# SD_Card.net
KiCad netlist of a schematic drawn in EasyEDA
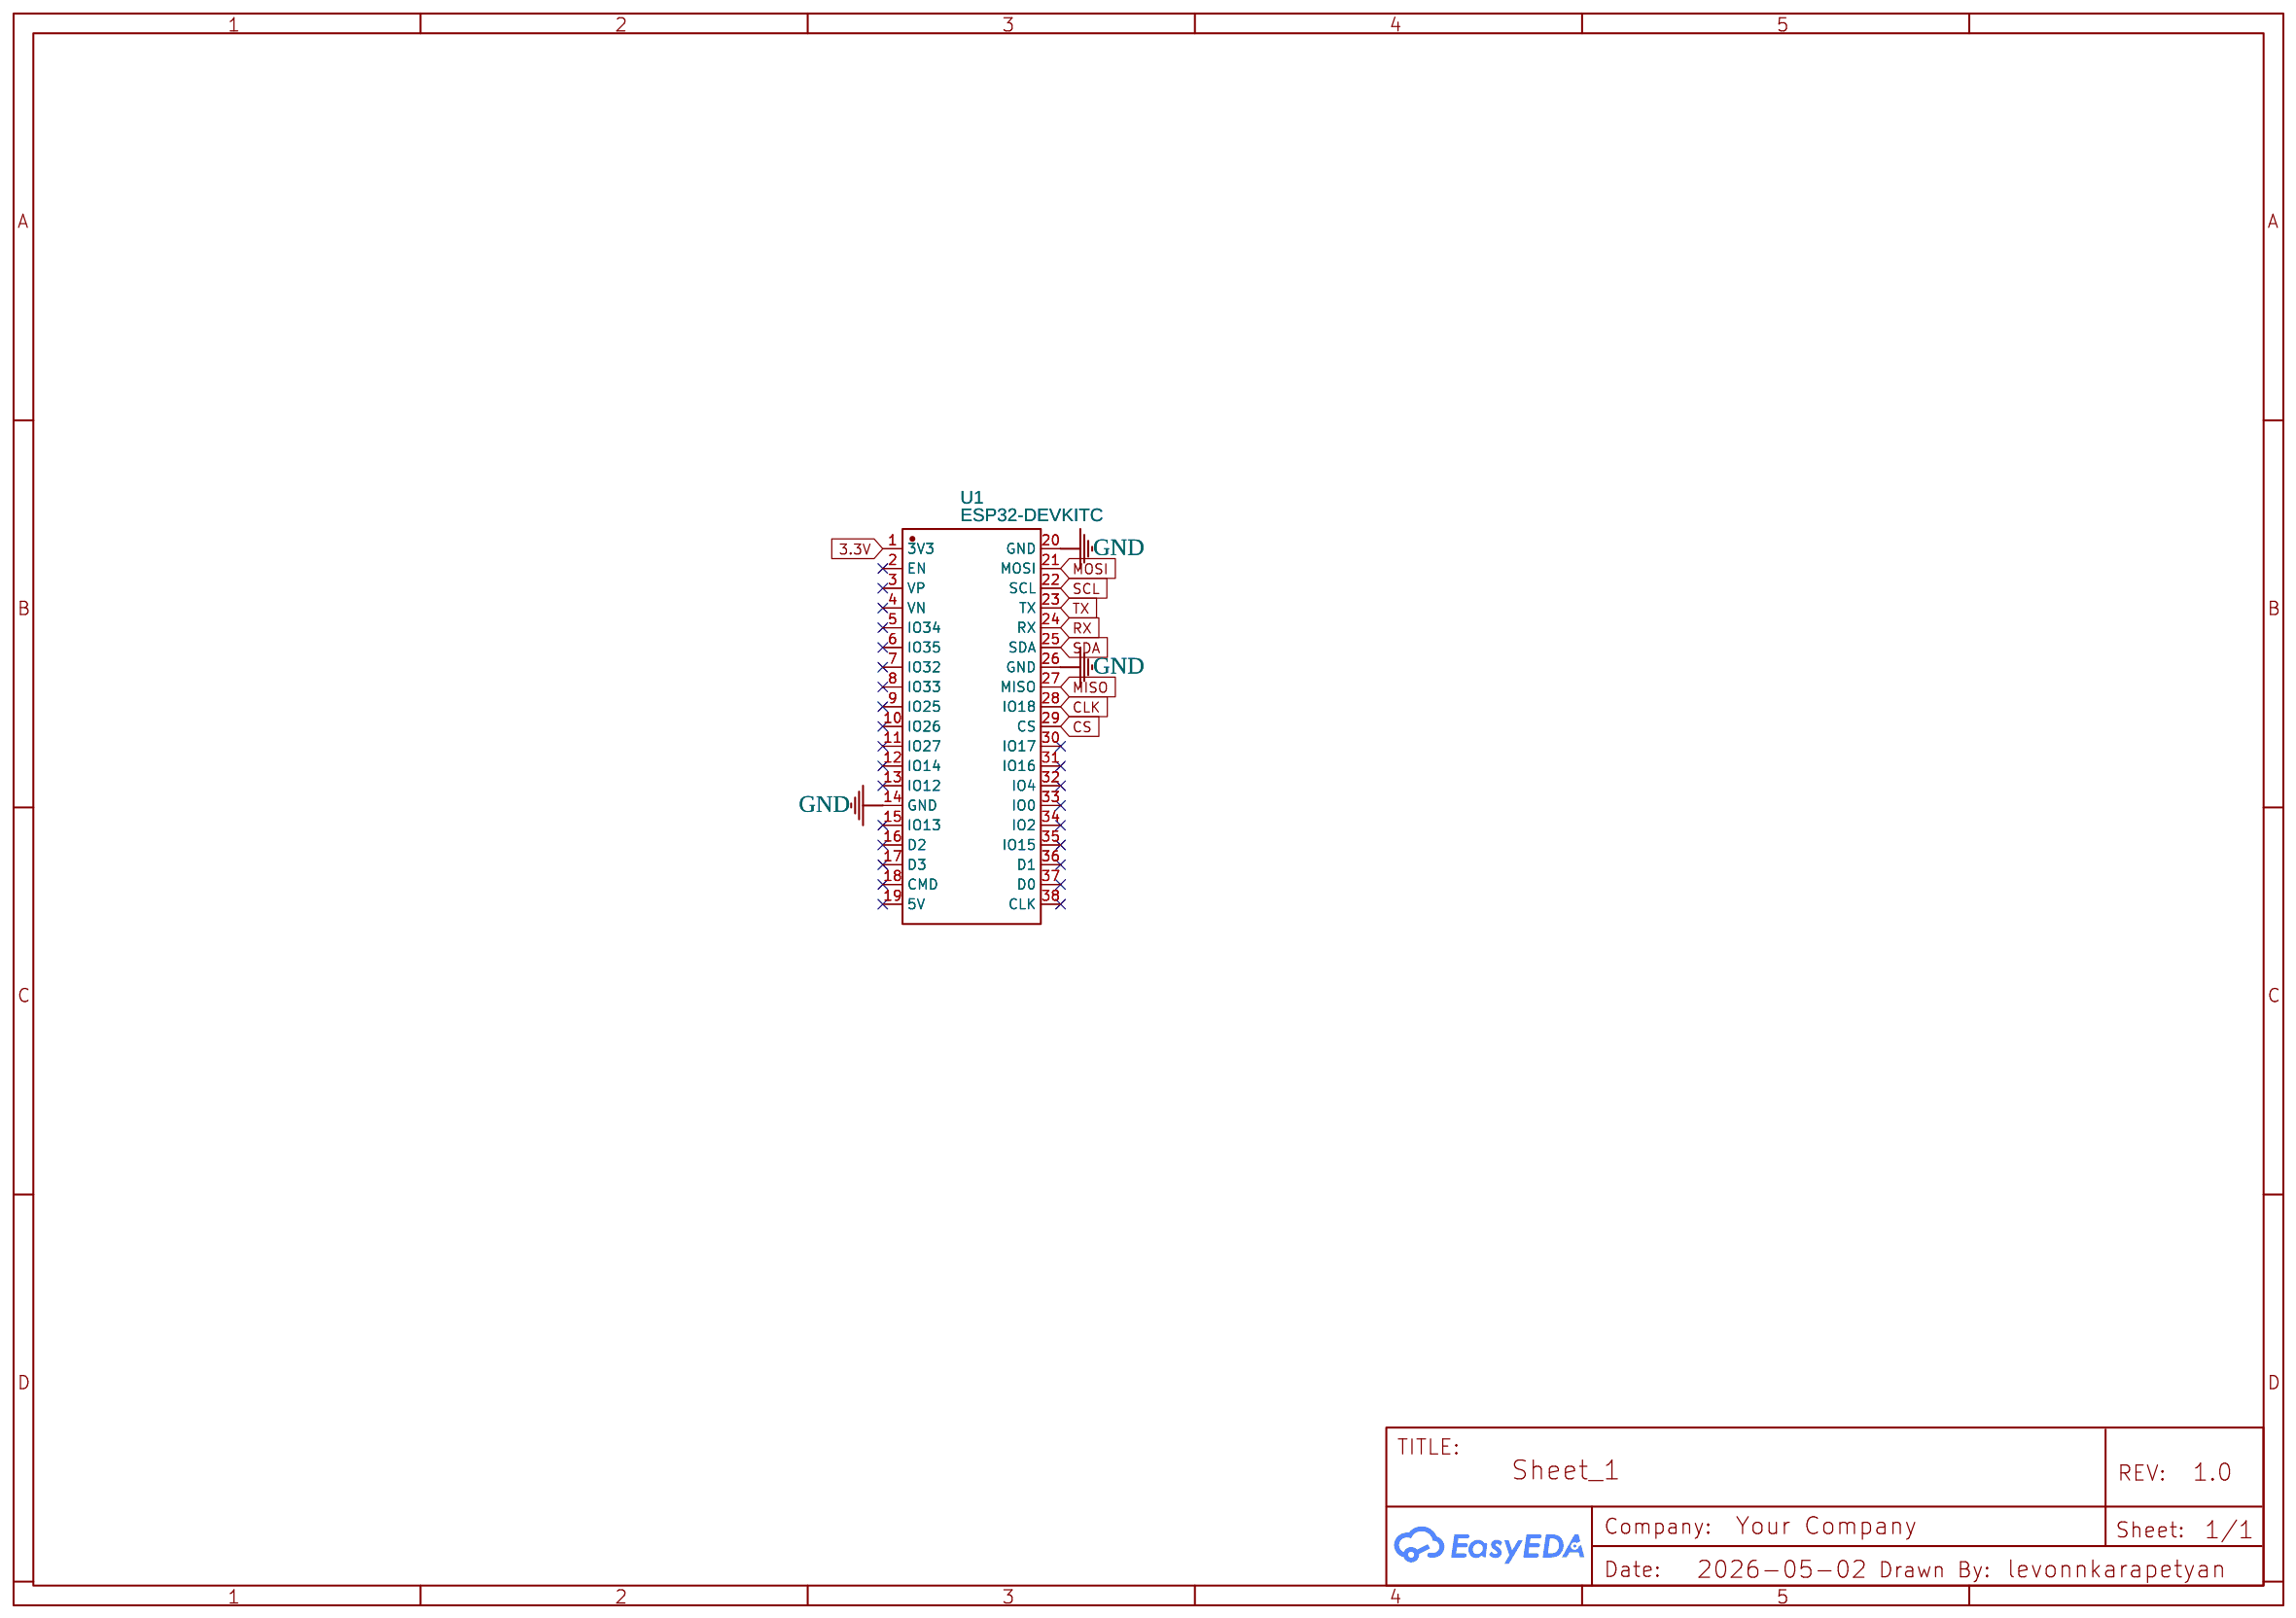
[diagram p0: ESP32]
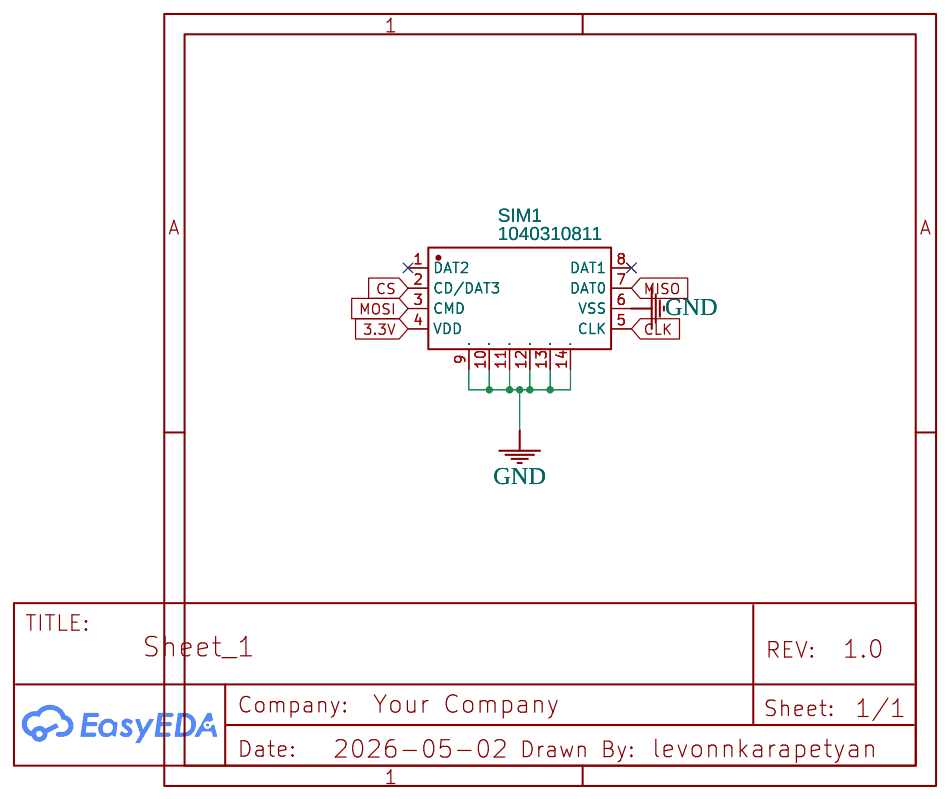
[diagram p1: SD_CARD]
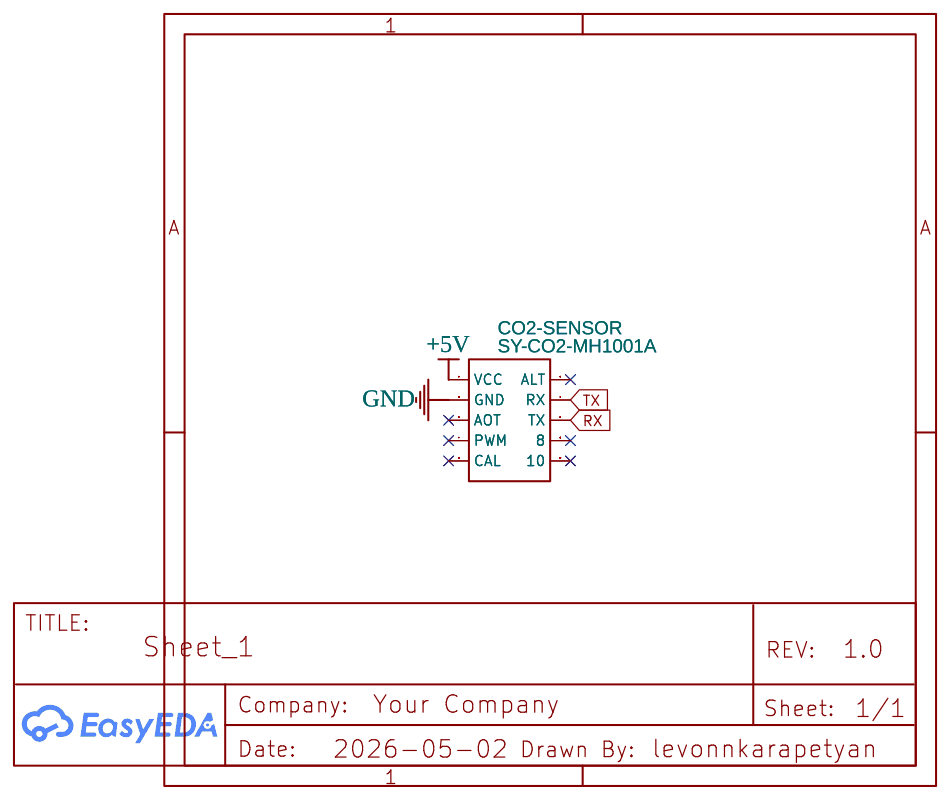
[diagram p2: CO2_sensor]
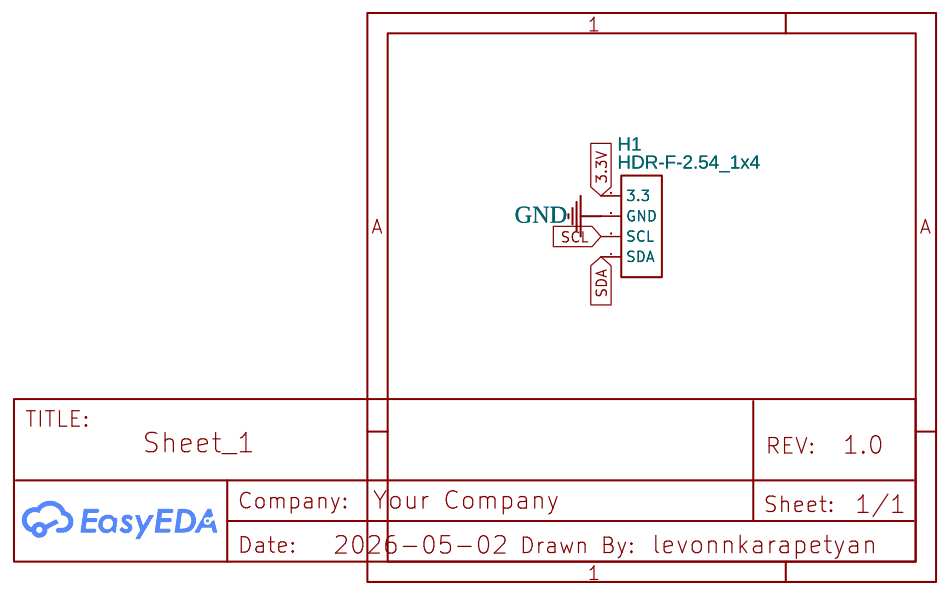
[diagram p3: BME280]
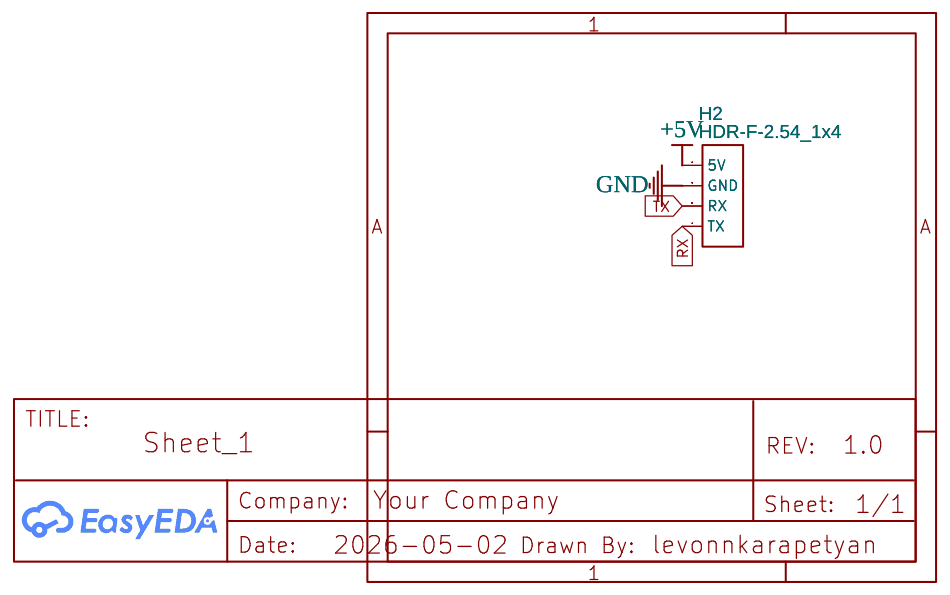
[diagram p4: PMS5003]
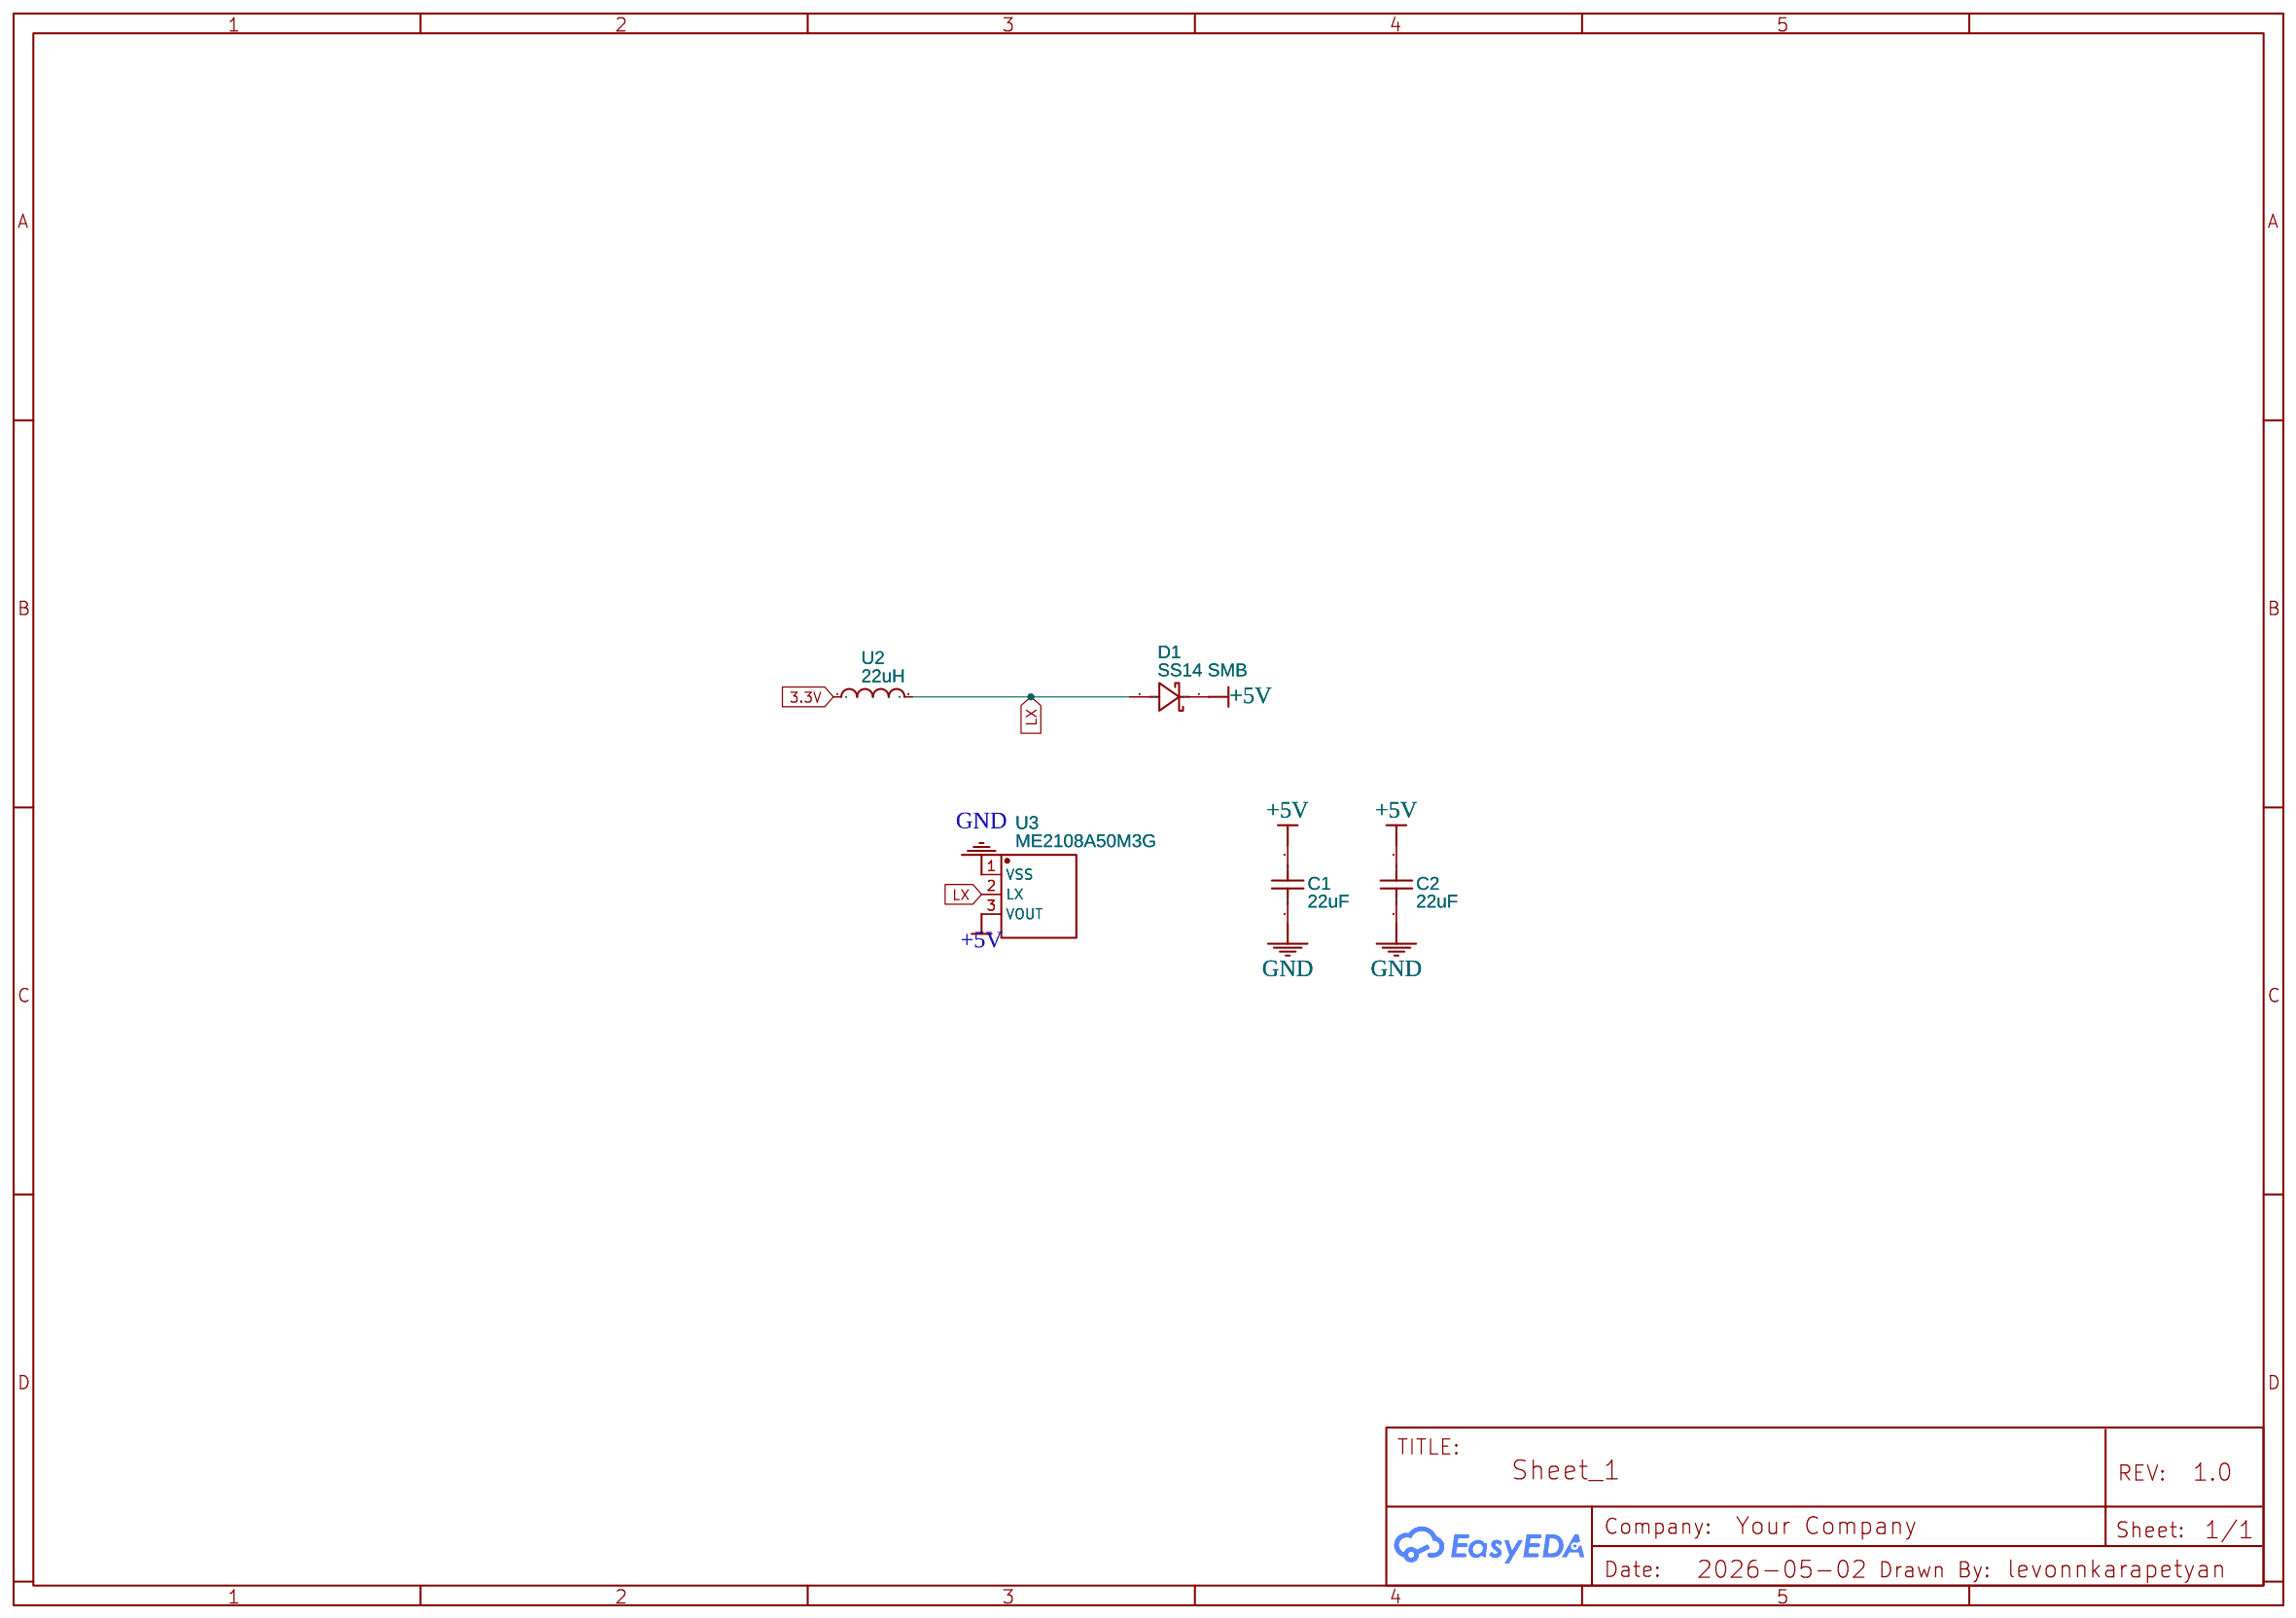
[diagram p5: Booster]

(export (version "E")
  (design (tool "Eeschema 10.0.6"))
  (components
    (comp (ref "U1")
      (value "ESP32-DEVKITC")
      (fields
        (field (name "Manufacturer Part") "ESP32-DevKitC")
        (field (name "Manufacturer") "ESPRESSIF(乐鑫)")
      )
      (libsource (lib "") (part "ESP32-DEVKITC"))
    )
    (comp (ref "SIM1")
      (value "1040310811")
      (fields (field (name "Manufacturer") "MOLEX"))
      (libsource (lib "") (part "1040310811"))
    )
    (comp (ref "CO2-SENSOR") (value "SY-CO2-MH1001A") (libsource (lib "") (part "HDR-F-2.54_2x5")))
    (comp (ref "H1") (value "HDR-F-2.54_1x4") (libsource (lib "") (part "HDR-F-2.54_1x4")))
    (comp (ref "H2") (value "HDR-F-2.54_1x4") (libsource (lib "") (part "HDR-F-2.54_1x4")))
    (comp (ref "C1")
      (value "22uF")
      (fields
        (field (name "Manufacturer Part") "CL21A226MAYNNNE")
        (field (name "Manufacturer") "SAMSUNG(三星)")
      )
      (libsource (lib "") (part "CL21A226MAYNNNE"))
    )
    (comp (ref "C2")
      (value "22uF")
      (fields
        (field (name "Manufacturer Part") "CL21A226MAYNNNE")
        (field (name "Manufacturer") "SAMSUNG(三星)")
      )
      (libsource (lib "") (part "CL21A226MAYNNNE"))
    )
    (comp (ref "D1")
      (value "SS14 SMB")
      (fields (field (name "Manufacturer") "BORN(伯恩半导体)"))
      (libsource (lib "") (part "SS14 SMB"))
    )
    (comp (ref "U2")
      (value "22uH")
      (fields (field (name "Manufacturer Part") "APH0630T220M") (field (name "Manufacturer") "APV(爱普微)"))
      (libsource (lib "") (part "APH0630T220M"))
    )
    (comp (ref "U3")
      (value "ME2108A50M3G")
      (fields (field (name "Manufacturer") "MICRONE(南京微盟)"))
      (libsource (lib "") (part "ME2108A50M3G"))
    )
  )
  (nets
    (net (code "1") (name "+5V") (class "Default")
      (node (ref "C1") (pin "2") (pinfunction "2_2") (pintype "unspecified"))
      (node (ref "C2") (pin "2") (pinfunction "2_2") (pintype "unspecified"))
      (node (ref "CO2-SENSOR") (pin "1") (pinfunction "VCC_1") (pintype "unspecified"))
      (node (ref "D1") (pin "1") (pinfunction "K_1") (pintype "unspecified"))
      (node (ref "H2") (pin "1") (pinfunction "5V_1") (pintype "unspecified"))
      (node (ref "U3") (pin "3") (pinfunction "VOUT_3") (pintype "unspecified"))
    )
    (net (code "2") (name "3.3V") (class "Default")
      (node (ref "H1") (pin "1") (pinfunction "3.3_1") (pintype "unspecified"))
      (node (ref "SIM1") (pin "4") (pinfunction "VDD_4") (pintype "unspecified"))
      (node (ref "U1") (pin "1") (pinfunction "3V3_1") (pintype "unspecified"))
      (node (ref "U2") (pin "1") (pinfunction "1_1") (pintype "unspecified"))
    )
    (net (code "3") (name "CLK") (class "Default")
      (node (ref "SIM1") (pin "5") (pinfunction "CLK_5") (pintype "unspecified"))
      (node (ref "U1") (pin "28") (pinfunction "IO18_28") (pintype "unspecified"))
    )
    (net (code "4") (name "CS") (class "Default")
      (node (ref "SIM1") (pin "2") (pinfunction "CD/DAT3_2") (pintype "unspecified"))
      (node (ref "U1") (pin "29") (pinfunction "CS_29") (pintype "unspecified"))
    )
    (net (code "5") (name "GND") (class "Default")
      (node (ref "C1") (pin "1") (pinfunction "1_1") (pintype "unspecified"))
      (node (ref "C2") (pin "1") (pinfunction "1_1") (pintype "unspecified"))
      (node (ref "CO2-SENSOR") (pin "3") (pinfunction "GND_3") (pintype "unspecified"))
      (node (ref "H1") (pin "2") (pinfunction "GND_2") (pintype "unspecified"))
      (node (ref "H2") (pin "2") (pinfunction "GND_2") (pintype "unspecified"))
      (node (ref "SIM1") (pin "10") (pinfunction "10_10") (pintype "unspecified"))
      (node (ref "SIM1") (pin "11") (pinfunction "11_11") (pintype "unspecified"))
      (node (ref "SIM1") (pin "12") (pinfunction "12_12") (pintype "unspecified"))
      (node (ref "SIM1") (pin "13") (pinfunction "13_13") (pintype "unspecified"))
      (node (ref "SIM1") (pin "14") (pinfunction "14_14") (pintype "unspecified"))
      (node (ref "SIM1") (pin "6") (pinfunction "VSS_6") (pintype "unspecified"))
      (node (ref "SIM1") (pin "9") (pinfunction "9_9") (pintype "unspecified"))
      (node (ref "U1") (pin "14") (pinfunction "GND_14") (pintype "unspecified"))
      (node (ref "U1") (pin "20") (pinfunction "GND_20") (pintype "unspecified"))
      (node (ref "U1") (pin "26") (pinfunction "GND_26") (pintype "unspecified"))
      (node (ref "U3") (pin "1") (pinfunction "VSS_1") (pintype "unspecified"))
    )
    (net (code "6") (name "LX") (class "Default")
      (node (ref "D1") (pin "2") (pinfunction "A_2") (pintype "unspecified"))
      (node (ref "U2") (pin "2") (pinfunction "2_2") (pintype "unspecified"))
      (node (ref "U3") (pin "2") (pinfunction "LX_2") (pintype "unspecified"))
    )
    (net (code "7") (name "MISO") (class "Default")
      (node (ref "SIM1") (pin "7") (pinfunction "DAT0_7") (pintype "unspecified"))
      (node (ref "U1") (pin "27") (pinfunction "MISO_27") (pintype "unspecified"))
    )
    (net (code "8") (name "MOSI") (class "Default")
      (node (ref "SIM1") (pin "3") (pinfunction "CMD_3") (pintype "unspecified"))
      (node (ref "U1") (pin "21") (pinfunction "MOSI_21") (pintype "unspecified"))
    )
    (net (code "9") (name "RX") (class "Default")
      (node (ref "CO2-SENSOR") (pin "6") (pinfunction "TX_6") (pintype "unspecified"))
      (node (ref "H2") (pin "4") (pinfunction "TX_4") (pintype "unspecified"))
      (node (ref "U1") (pin "24") (pinfunction "RX_24") (pintype "unspecified"))
    )
    (net (code "10") (name "SCL") (class "Default")
      (node (ref "H1") (pin "3") (pinfunction "SCL_3") (pintype "unspecified"))
      (node (ref "U1") (pin "22") (pinfunction "SCL_22") (pintype "unspecified"))
    )
    (net (code "11") (name "SDA") (class "Default")
      (node (ref "H1") (pin "4") (pinfunction "SDA_4") (pintype "unspecified"))
      (node (ref "U1") (pin "25") (pinfunction "SDA_25") (pintype "unspecified"))
    )
    (net (code "12") (name "TX") (class "Default")
      (node (ref "CO2-SENSOR") (pin "4") (pinfunction "RX_4") (pintype "unspecified"))
      (node (ref "H2") (pin "3") (pinfunction "RX_3") (pintype "unspecified"))
      (node (ref "U1") (pin "23") (pinfunction "TX_23") (pintype "unspecified"))
    )
    (net (code "13") (name "unconnected-(CO2-SENSOR-ALT-Pad2)") (class "Default")
      (node (ref "CO2-SENSOR") (pin "2") (pinfunction "ALT_2") (pintype "unspecified+no_connect"))
    )
    (net (code "14") (name "unconnected-(CO2-SENSOR-AOT-Pad5)") (class "Default")
      (node (ref "CO2-SENSOR") (pin "5") (pinfunction "AOT_5") (pintype "unspecified+no_connect"))
    )
    (net (code "15") (name "unconnected-(CO2-SENSOR-CAL-Pad9)") (class "Default")
      (node (ref "CO2-SENSOR") (pin "9") (pinfunction "CAL_9") (pintype "unspecified+no_connect"))
    )
    (net (code "16") (name "unconnected-(CO2-SENSOR-PWM-Pad7)") (class "Default")
      (node (ref "CO2-SENSOR") (pin "7") (pinfunction "PWM_7") (pintype "unspecified+no_connect"))
    )
    (net (code "17") (name "unconnected-(CO2-SENSOR-Pad8)") (class "Default")
      (node (ref "CO2-SENSOR") (pin "8") (pinfunction "8_8") (pintype "unspecified+no_connect"))
    )
    (net (code "18") (name "unconnected-(CO2-SENSOR-Pad10)") (class "Default")
      (node (ref "CO2-SENSOR") (pin "10") (pinfunction "10_10") (pintype "unspecified+no_connect"))
    )
    (net (code "19") (name "unconnected-(SIM1-DAT1-Pad8)") (class "Default")
      (node (ref "SIM1") (pin "8") (pinfunction "DAT1_8") (pintype "unspecified+no_connect"))
    )
    (net (code "20") (name "unconnected-(SIM1-DAT2-Pad1)") (class "Default")
      (node (ref "SIM1") (pin "1") (pinfunction "DAT2_1") (pintype "unspecified+no_connect"))
    )
    (net (code "21") (name "unconnected-(U1-5V-Pad19)") (class "Default")
      (node (ref "U1") (pin "19") (pinfunction "5V_19") (pintype "unspecified+no_connect"))
    )
    (net (code "22") (name "unconnected-(U1-CLK-Pad38)") (class "Default")
      (node (ref "U1") (pin "38") (pinfunction "CLK_38") (pintype "unspecified+no_connect"))
    )
    (net (code "23") (name "unconnected-(U1-CMD-Pad18)") (class "Default")
      (node (ref "U1") (pin "18") (pinfunction "CMD_18") (pintype "unspecified+no_connect"))
    )
    (net (code "24") (name "unconnected-(U1-D0-Pad37)") (class "Default")
      (node (ref "U1") (pin "37") (pinfunction "D0_37") (pintype "unspecified+no_connect"))
    )
    (net (code "25") (name "unconnected-(U1-D1-Pad36)") (class "Default")
      (node (ref "U1") (pin "36") (pinfunction "D1_36") (pintype "unspecified+no_connect"))
    )
    (net (code "26") (name "unconnected-(U1-D2-Pad16)") (class "Default")
      (node (ref "U1") (pin "16") (pinfunction "D2_16") (pintype "unspecified+no_connect"))
    )
    (net (code "27") (name "unconnected-(U1-D3-Pad17)") (class "Default")
      (node (ref "U1") (pin "17") (pinfunction "D3_17") (pintype "unspecified+no_connect"))
    )
    (net (code "28") (name "unconnected-(U1-EN-Pad2)") (class "Default")
      (node (ref "U1") (pin "2") (pinfunction "EN_2") (pintype "unspecified+no_connect"))
    )
    (net (code "29") (name "unconnected-(U1-IO0-Pad33)") (class "Default")
      (node (ref "U1") (pin "33") (pinfunction "IO0_33") (pintype "unspecified+no_connect"))
    )
    (net (code "30") (name "unconnected-(U1-IO2-Pad34)") (class "Default")
      (node (ref "U1") (pin "34") (pinfunction "IO2_34") (pintype "unspecified+no_connect"))
    )
    (net (code "31") (name "unconnected-(U1-IO4-Pad32)") (class "Default")
      (node (ref "U1") (pin "32") (pinfunction "IO4_32") (pintype "unspecified+no_connect"))
    )
    (net (code "32") (name "unconnected-(U1-IO12-Pad13)") (class "Default")
      (node (ref "U1") (pin "13") (pinfunction "IO12_13") (pintype "unspecified+no_connect"))
    )
    (net (code "33") (name "unconnected-(U1-IO13-Pad15)") (class "Default")
      (node (ref "U1") (pin "15") (pinfunction "IO13_15") (pintype "unspecified+no_connect"))
    )
    (net (code "34") (name "unconnected-(U1-IO14-Pad12)") (class "Default")
      (node (ref "U1") (pin "12") (pinfunction "IO14_12") (pintype "unspecified+no_connect"))
    )
    (net (code "35") (name "unconnected-(U1-IO15-Pad35)") (class "Default")
      (node (ref "U1") (pin "35") (pinfunction "IO15_35") (pintype "unspecified+no_connect"))
    )
    (net (code "36") (name "unconnected-(U1-IO16-Pad31)") (class "Default")
      (node (ref "U1") (pin "31") (pinfunction "IO16_31") (pintype "unspecified+no_connect"))
    )
    (net (code "37") (name "unconnected-(U1-IO17-Pad30)") (class "Default")
      (node (ref "U1") (pin "30") (pinfunction "IO17_30") (pintype "unspecified+no_connect"))
    )
    (net (code "38") (name "unconnected-(U1-IO25-Pad9)") (class "Default")
      (node (ref "U1") (pin "9") (pinfunction "IO25_9") (pintype "unspecified+no_connect"))
    )
    (net (code "39") (name "unconnected-(U1-IO26-Pad10)") (class "Default")
      (node (ref "U1") (pin "10") (pinfunction "IO26_10") (pintype "unspecified+no_connect"))
    )
    (net (code "40") (name "unconnected-(U1-IO27-Pad11)") (class "Default")
      (node (ref "U1") (pin "11") (pinfunction "IO27_11") (pintype "unspecified+no_connect"))
    )
    (net (code "41") (name "unconnected-(U1-IO32-Pad7)") (class "Default")
      (node (ref "U1") (pin "7") (pinfunction "IO32_7") (pintype "unspecified+no_connect"))
    )
    (net (code "42") (name "unconnected-(U1-IO33-Pad8)") (class "Default")
      (node (ref "U1") (pin "8") (pinfunction "IO33_8") (pintype "unspecified+no_connect"))
    )
    (net (code "43") (name "unconnected-(U1-IO34-Pad5)") (class "Default")
      (node (ref "U1") (pin "5") (pinfunction "IO34_5") (pintype "unspecified+no_connect"))
    )
    (net (code "44") (name "unconnected-(U1-IO35-Pad6)") (class "Default")
      (node (ref "U1") (pin "6") (pinfunction "IO35_6") (pintype "unspecified+no_connect"))
    )
    (net (code "45") (name "unconnected-(U1-VN-Pad4)") (class "Default")
      (node (ref "U1") (pin "4") (pinfunction "VN_4") (pintype "unspecified+no_connect"))
    )
    (net (code "46") (name "unconnected-(U1-VP-Pad3)") (class "Default")
      (node (ref "U1") (pin "3") (pinfunction "VP_3") (pintype "unspecified+no_connect"))
    )
  )
)
